# BUFFER_ATOB.net
KiCad netlist of a schematic drawn in Altium Designer
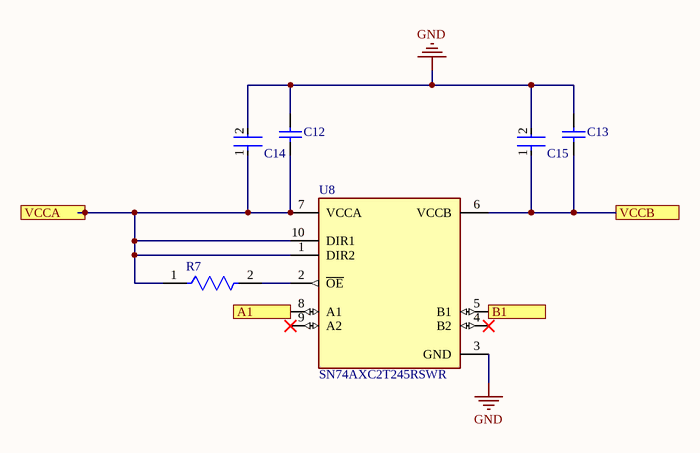
[diagram p0: BUFFER_ATOB.SchDoc]

(export (version "E")
  (design (tool "Eeschema 10.0.6"))
  (components
    (comp (ref "C12")
      (value "CAP 1uF 16V 0805(2012)")
      (footprint "CAPC0805(2012)100_N")
      (description "CAP 1uF 16V ±10% 0805 (2012 Metric) Thickness 1mm SMD")
      (fields (field (name "TOLERANCE") "Â±10%") (field (name "MANUFACTURER") "KEMET"))
      (libsource (lib "Altium Content Vault") (part "CAP"))
    )
    (comp (ref "C13")
      (value "CAP 1uF 16V 0805(2012)")
      (footprint "CAPC0805(2012)100_N")
      (description "CAP 1uF 16V ±10% 0805 (2012 Metric) Thickness 1mm SMD")
      (fields (field (name "TOLERANCE") "Â±10%") (field (name "MANUFACTURER") "KEMET"))
      (libsource (lib "Altium Content Vault") (part "CAP"))
    )
    (comp (ref "C14")
      (value "C0805C104K4RAC")
      (footprint "FP-C0805C-DN-MFG")
      (description "C0805 0.10 μF X7R 30ppm/°C 10.00% 16 V")
      (fields
        (field (name "TOLERANCE") "0.1")
        (field (name "OCTOPART") "https://octopart.com/c0805c104k4rac-kemet-1343167")
      )
      (libsource (lib "Altium Content Vault") (part "b4654b650e69147ec39a6b967a45e02"))
    )
    (comp (ref "C15")
      (value "C0805C104K4RAC")
      (footprint "FP-C0805C-DN-MFG")
      (description "C0805 0.10 μF X7R 30ppm/°C 10.00% 16 V")
      (fields
        (field (name "TOLERANCE") "0.1")
        (field (name "OCTOPART") "https://octopart.com/c0805c104k4rac-kemet-1343167")
      )
      (libsource (lib "Altium Content Vault") (part "b4654b650e69147ec39a6b967a45e02"))
    )
    (comp (ref "R7")
      (value "RC0603FR-0710KL")
      (footprint "FP-RC0603-0_55-IPC_C")
      (description "RES 10K OHM 1% 1/10W 0603")
      (fields (field (name "TOLERANCE") "1%") (field (name "MANUFACTURER") "Yageo"))
      (libsource (lib "Altium Content Vault") (part "1029c3af85768c4190bb7ad29bc67b5"))
    )
    (comp (ref "U8")
      (value "SN74AXC2T245RSWR")
      (footprint "FP-RSW0010A-MFG")
      (description "DUAL-BIT, 2-DIR PIN DUAL-SUPPLY")
      (fields (field (name "MANUFACTURER") "Texas Instruments"))
      (libsource (lib "Altium Content Vault") (part "83d821090a53739ef2c335e5778ad4a"))
    )
  )
  (nets
    (net (code "1") (name "/A1") (class "Default")
      (node (ref "U8") (pin "8") (pinfunction "A1_8") (pintype "bidirectional"))
    )
    (net (code "2") (name "/B1") (class "Default")
      (node (ref "U8") (pin "5") (pinfunction "B1_5") (pintype "bidirectional"))
    )
    (net (code "3") (name "/VCCA") (class "Default")
      (node (ref "C12") (pin "1") (pinfunction "1_1") (pintype "passive"))
      (node (ref "C14") (pin "1") (pinfunction "1_1") (pintype "passive"))
      (node (ref "R7") (pin "1") (pinfunction "1_1") (pintype "passive"))
      (node (ref "U8") (pin "1") (pinfunction "DIR2_1") (pintype "passive"))
      (node (ref "U8") (pin "10") (pinfunction "DIR1_10") (pintype "passive"))
      (node (ref "U8") (pin "7") (pinfunction "VCCA_7") (pintype "power_in"))
    )
    (net (code "4") (name "/VCCB") (class "Default")
      (node (ref "C13") (pin "1") (pinfunction "1_1") (pintype "passive"))
      (node (ref "C15") (pin "1") (pinfunction "1_1") (pintype "passive"))
      (node (ref "U8") (pin "6") (pinfunction "VCCB_6") (pintype "power_in"))
    )
    (net (code "5") (name "GND") (class "Default")
      (node (ref "C12") (pin "2") (pinfunction "2_2") (pintype "passive"))
      (node (ref "C13") (pin "2") (pinfunction "2_2") (pintype "passive"))
      (node (ref "C14") (pin "2") (pinfunction "2_2") (pintype "passive"))
      (node (ref "C15") (pin "2") (pinfunction "2_2") (pintype "passive"))
      (node (ref "U8") (pin "3") (pinfunction "GND_3") (pintype "power_in"))
    )
    (net (code "6") (name "Net-(U8-~{OE})") (class "Default")
      (node (ref "R7") (pin "2") (pinfunction "2_2") (pintype "passive"))
      (node (ref "U8") (pin "2") (pinfunction "~{OE}_2") (pintype "output"))
    )
    (net (code "7") (name "unconnected-(U8-A2-Pad9)") (class "Default")
      (node (ref "U8") (pin "9") (pinfunction "A2_9") (pintype "bidirectional+no_connect"))
    )
    (net (code "8") (name "unconnected-(U8-B2-Pad4)") (class "Default")
      (node (ref "U8") (pin "4") (pinfunction "B2_4") (pintype "bidirectional+no_connect"))
    )
  )
)
